# zapojeni.net
KiCad netlist of a schematic drawn in EAGLE
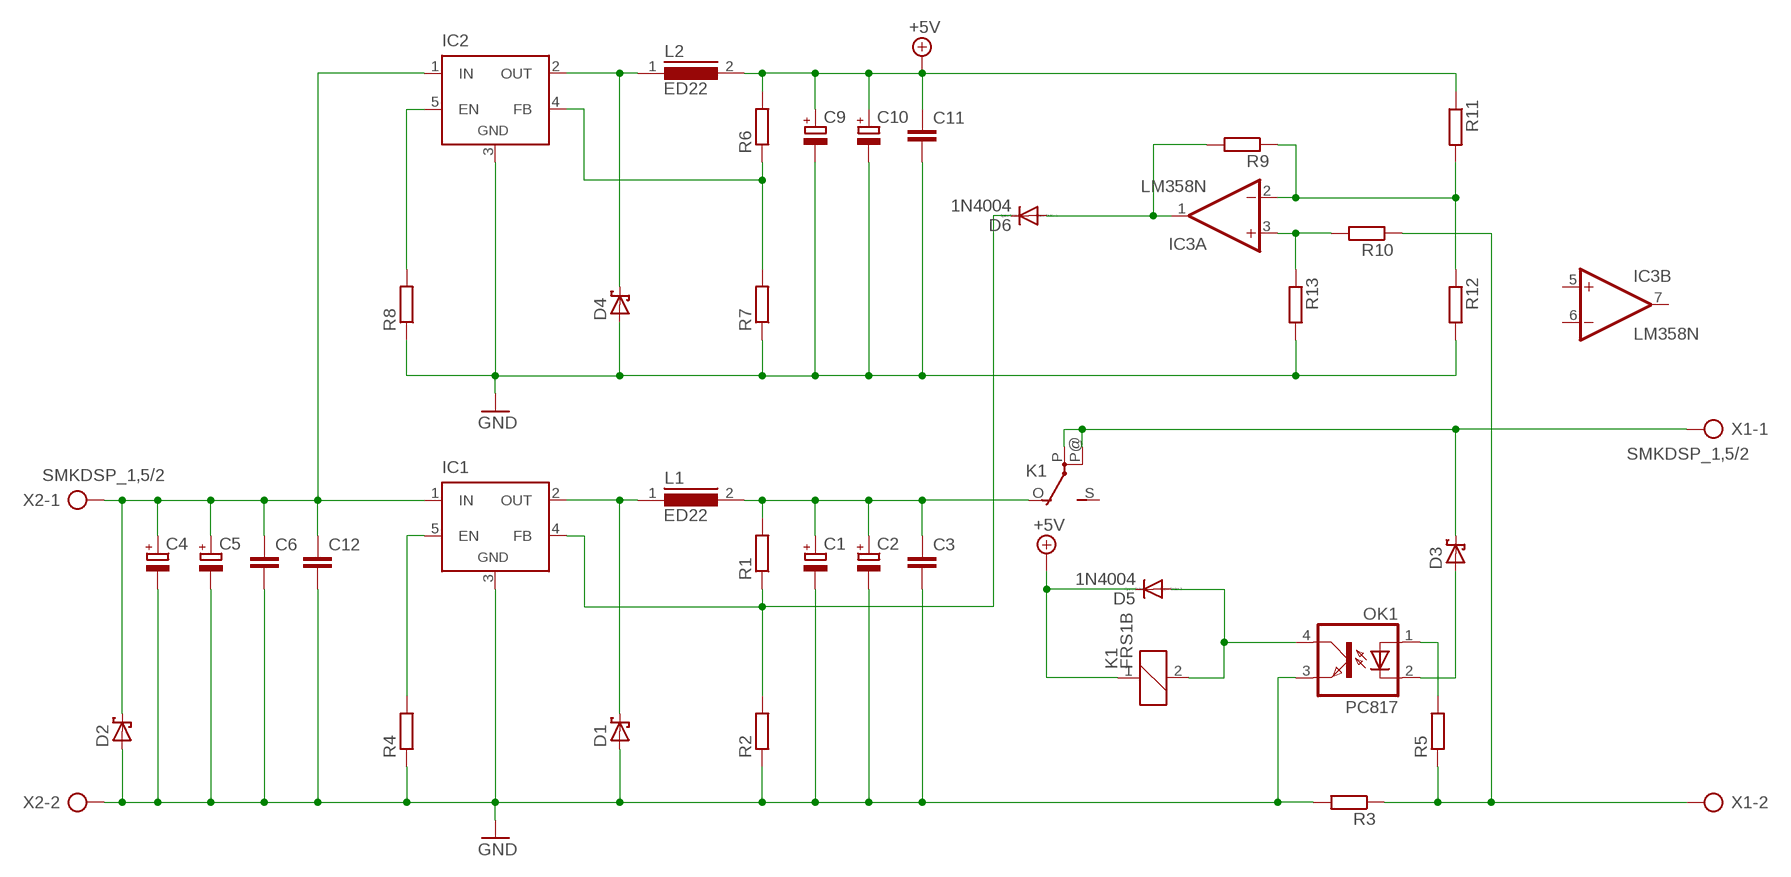
[diagram p0: schematic, sheet 1]

(export (version "E")
  (design (tool "Eeschema 10.0.6"))
  (components
    (comp (ref "C1")
      (value "CPOL-EUE5-8.5")
      (footprint "eagle-import:E5-8,5")
      (libsource (lib "eagle-import") (part "CPOL-EUE5-8.5"))
    )
    (comp (ref "C2")
      (value "CPOL-EUE5-8.5")
      (footprint "eagle-import:E5-8,5")
      (libsource (lib "eagle-import") (part "CPOL-EUE5-8.5"))
    )
    (comp (ref "C3")
      (value "C-EU050-035X075")
      (footprint "eagle-import:C050-035X075")
      (libsource (lib "eagle-import") (part "C-EU050-035X075"))
    )
    (comp (ref "C4")
      (value "CPOL-EUE5-8.5")
      (footprint "eagle-import:E5-8,5")
      (libsource (lib "eagle-import") (part "CPOL-EUE5-8.5"))
    )
    (comp (ref "C5")
      (value "CPOL-EUE5-8.5")
      (footprint "eagle-import:E5-8,5")
      (libsource (lib "eagle-import") (part "CPOL-EUE5-8.5"))
    )
    (comp (ref "C6")
      (value "C-EU050-035X075")
      (footprint "eagle-import:C050-035X075")
      (libsource (lib "eagle-import") (part "C-EU050-035X075"))
    )
    (comp (ref "C9")
      (value "CPOL-EUE5-8.5")
      (footprint "eagle-import:E5-8,5")
      (libsource (lib "eagle-import") (part "CPOL-EUE5-8.5"))
    )
    (comp (ref "C10")
      (value "CPOL-EUE5-8.5")
      (footprint "eagle-import:E5-8,5")
      (libsource (lib "eagle-import") (part "CPOL-EUE5-8.5"))
    )
    (comp (ref "C11")
      (value "C-EU050-035X075")
      (footprint "eagle-import:C050-035X075")
      (libsource (lib "eagle-import") (part "C-EU050-035X075"))
    )
    (comp (ref "C12")
      (value "C-EU050-035X075")
      (footprint "eagle-import:C050-035X075")
      (libsource (lib "eagle-import") (part "C-EU050-035X075"))
    )
    (comp (ref "D1")
      (value "SCHOTTKY-DIODEDO201T15")
      (footprint "eagle-import:DO201T15")
      (libsource (lib "eagle-import") (part "SCHOTTKY-DIODEDO201T15"))
    )
    (comp (ref "D2")
      (value "SCHOTTKY-DIODEDO201T15")
      (footprint "eagle-import:DO201T15")
      (libsource (lib "eagle-import") (part "SCHOTTKY-DIODEDO201T15"))
    )
    (comp (ref "D3")
      (value "SCHOTTKY-DIODEDO201T15")
      (footprint "eagle-import:DO201T15")
      (libsource (lib "eagle-import") (part "SCHOTTKY-DIODEDO201T15"))
    )
    (comp (ref "D4")
      (value "SCHOTTKY-DIODEDO201T15")
      (footprint "eagle-import:DO201T15")
      (libsource (lib "eagle-import") (part "SCHOTTKY-DIODEDO201T15"))
    )
    (comp (ref "D5")
      (value "1N4004")
      (footprint "eagle-import:DO41-10")
      (libsource (lib "eagle-import") (part "1N4004"))
    )
    (comp (ref "D6")
      (value "1N4004")
      (footprint "eagle-import:DO41-10")
      (libsource (lib "eagle-import") (part "1N4004"))
    )
    (comp (ref "IC1")
      (value "LM2596TH")
      (footprint "eagle-import:TO220-52")
      (libsource (lib "eagle-import") (part "LM2596TH"))
    )
    (comp (ref "IC2")
      (value "LM2596TH")
      (footprint "eagle-import:TO220-52")
      (libsource (lib "eagle-import") (part "LM2596TH"))
    )
    (comp (ref "IC3")
      (value "LM358N")
      (footprint "eagle-import:DIL08")
      (libsource (lib "eagle-import") (part "LM358N"))
    )
    (comp (ref "K1")
      (value "FRS1B")
      (footprint "eagle-import:FRS1B")
      (libsource (lib "eagle-import") (part "FRS1B"))
    )
    (comp (ref "L1")
      (value "ED22")
      (footprint "eagle-import:ED22")
      (libsource (lib "eagle-import") (part "ED22"))
    )
    (comp (ref "L2")
      (value "ED22")
      (footprint "eagle-import:ED22")
      (libsource (lib "eagle-import") (part "ED22"))
    )
    (comp (ref "OK1")
      (value "PC817")
      (footprint "eagle-import:DIL04")
      (fields (field (name "MPN") "PC817X4J000F"))
      (libsource (lib "eagle-import") (part "PC817"))
    )
    (comp (ref "R1")
      (value "R-EU_0207/10")
      (footprint "eagle-import:0207_10")
      (libsource (lib "eagle-import") (part "R-EU_0207/10"))
    )
    (comp (ref "R2")
      (value "R-EU_0207/10")
      (footprint "eagle-import:0207_10")
      (libsource (lib "eagle-import") (part "R-EU_0207/10"))
    )
    (comp (ref "R3")
      (value "R-EU_0207/10")
      (footprint "eagle-import:0207_10")
      (libsource (lib "eagle-import") (part "R-EU_0207/10"))
    )
    (comp (ref "R4")
      (value "R-EU_0207/10")
      (footprint "eagle-import:0207_10")
      (libsource (lib "eagle-import") (part "R-EU_0207/10"))
    )
    (comp (ref "R5")
      (value "R-EU_0207/10")
      (footprint "eagle-import:0207_10")
      (libsource (lib "eagle-import") (part "R-EU_0207/10"))
    )
    (comp (ref "R6")
      (value "R-EU_0207/10")
      (footprint "eagle-import:0207_10")
      (libsource (lib "eagle-import") (part "R-EU_0207/10"))
    )
    (comp (ref "R7")
      (value "R-EU_0207/10")
      (footprint "eagle-import:0207_10")
      (libsource (lib "eagle-import") (part "R-EU_0207/10"))
    )
    (comp (ref "R8")
      (value "R-EU_0207/10")
      (footprint "eagle-import:0207_10")
      (libsource (lib "eagle-import") (part "R-EU_0207/10"))
    )
    (comp (ref "R9")
      (value "R-EU_0207/10")
      (footprint "eagle-import:0207_10")
      (libsource (lib "eagle-import") (part "R-EU_0207/10"))
    )
    (comp (ref "R10")
      (value "R-EU_0207/10")
      (footprint "eagle-import:0207_10")
      (libsource (lib "eagle-import") (part "R-EU_0207/10"))
    )
    (comp (ref "R11")
      (value "R-EU_0207/10")
      (footprint "eagle-import:0207_10")
      (libsource (lib "eagle-import") (part "R-EU_0207/10"))
    )
    (comp (ref "R12")
      (value "R-EU_0207/10")
      (footprint "eagle-import:0207_10")
      (libsource (lib "eagle-import") (part "R-EU_0207/10"))
    )
    (comp (ref "R13")
      (value "R-EU_0207/10")
      (footprint "eagle-import:0207_10")
      (libsource (lib "eagle-import") (part "R-EU_0207/10"))
    )
    (comp (ref "X1")
      (value "SMKDSP_1,5/2")
      (footprint "eagle-import:SMKDSP_1,5_2")
      (fields (field (name "MF") "FARNELL") (field (name "MPN") "1733570"))
      (libsource (lib "eagle-import") (part "SMKDSP_1,5/2"))
    )
    (comp (ref "X2")
      (value "SMKDSP_1,5/2")
      (footprint "eagle-import:SMKDSP_1,5_2")
      (fields (field (name "MF") "FARNELL") (field (name "MPN") "1733570"))
      (libsource (lib "eagle-import") (part "SMKDSP_1,5/2"))
    )
  )
  (nets
    (net (code "1") (name "+5V") (class "Default")
      (node (ref "C10") (pin "+") (pinfunction "+_+") (pintype "passive"))
      (node (ref "C11") (pin "1") (pinfunction "1_1") (pintype "passive"))
      (node (ref "C9") (pin "+") (pinfunction "+_+") (pintype "passive"))
      (node (ref "D5") (pin "C") (pinfunction "C_C") (pintype "passive"))
      (node (ref "K1") (pin "1") (pinfunction "1_1") (pintype "passive"))
      (node (ref "L2") (pin "2") (pinfunction "2_2") (pintype "passive"))
      (node (ref "R11") (pin "1") (pinfunction "1_1") (pintype "passive"))
      (node (ref "R6") (pin "2") (pinfunction "2_2") (pintype "passive"))
    )
    (net (code "2") (name "GND") (class "Default")
      (node (ref "C1") (pin "-") (pinfunction "-_-") (pintype "passive"))
      (node (ref "C10") (pin "-") (pinfunction "-_-") (pintype "passive"))
      (node (ref "C11") (pin "2") (pinfunction "2_2") (pintype "passive"))
      (node (ref "C12") (pin "2") (pinfunction "2_2") (pintype "passive"))
      (node (ref "C2") (pin "-") (pinfunction "-_-") (pintype "passive"))
      (node (ref "C3") (pin "2") (pinfunction "2_2") (pintype "passive"))
      (node (ref "C4") (pin "-") (pinfunction "-_-") (pintype "passive"))
      (node (ref "C5") (pin "-") (pinfunction "-_-") (pintype "passive"))
      (node (ref "C6") (pin "2") (pinfunction "2_2") (pintype "passive"))
      (node (ref "C9") (pin "-") (pinfunction "-_-") (pintype "passive"))
      (node (ref "D1") (pin "A") (pinfunction "A_A") (pintype "passive"))
      (node (ref "D2") (pin "A") (pinfunction "A_A") (pintype "passive"))
      (node (ref "D4") (pin "A") (pinfunction "A_A") (pintype "passive"))
      (node (ref "IC1") (pin "3") (pinfunction "GND_3") (pintype "power_in"))
      (node (ref "IC2") (pin "3") (pinfunction "GND_3") (pintype "power_in"))
      (node (ref "OK1") (pin "3") (pinfunction "EMIT_3") (pintype "passive"))
      (node (ref "R12") (pin "2") (pinfunction "2_2") (pintype "passive"))
      (node (ref "R13") (pin "2") (pinfunction "2_2") (pintype "passive"))
      (node (ref "R2") (pin "1") (pinfunction "1_1") (pintype "passive"))
      (node (ref "R3") (pin "2") (pinfunction "2_2") (pintype "passive"))
      (node (ref "R4") (pin "1") (pinfunction "1_1") (pintype "passive"))
      (node (ref "R7") (pin "1") (pinfunction "1_1") (pintype "passive"))
      (node (ref "R8") (pin "1") (pinfunction "1_1") (pintype "passive"))
      (node (ref "X2") (pin "2") (pinfunction "KL_2") (pintype "passive"))
    )
    (net (code "3") (name "Net-(C1-Pad+)") (class "Default")
      (node (ref "C1") (pin "+") (pinfunction "+_+") (pintype "passive"))
      (node (ref "C2") (pin "+") (pinfunction "+_+") (pintype "passive"))
      (node (ref "C3") (pin "1") (pinfunction "1_1") (pintype "passive"))
      (node (ref "K1") (pin "O") (pinfunction "O_O") (pintype "passive"))
      (node (ref "L1") (pin "2") (pinfunction "2_2") (pintype "passive"))
      (node (ref "R1") (pin "2") (pinfunction "2_2") (pintype "passive"))
    )
    (net (code "4") (name "Net-(IC1-EN)") (class "Default")
      (node (ref "IC1") (pin "5") (pinfunction "EN_5") (pintype "input"))
      (node (ref "R4") (pin "2") (pinfunction "2_2") (pintype "passive"))
    )
    (net (code "5") (name "Net-(IC1-FB)") (class "Default")
      (node (ref "D6") (pin "C") (pinfunction "C_C") (pintype "passive"))
      (node (ref "IC1") (pin "4") (pinfunction "FB_4") (pintype "input"))
      (node (ref "R1") (pin "1") (pinfunction "1_1") (pintype "passive"))
      (node (ref "R2") (pin "2") (pinfunction "2_2") (pintype "passive"))
    )
    (net (code "6") (name "Net-(IC1-IN)") (class "Default")
      (node (ref "C12") (pin "1") (pinfunction "1_1") (pintype "passive"))
      (node (ref "C4") (pin "+") (pinfunction "+_+") (pintype "passive"))
      (node (ref "C5") (pin "+") (pinfunction "+_+") (pintype "passive"))
      (node (ref "C6") (pin "1") (pinfunction "1_1") (pintype "passive"))
      (node (ref "D2") (pin "C") (pinfunction "C_C") (pintype "passive"))
      (node (ref "IC1") (pin "1") (pinfunction "IN_1") (pintype "input"))
      (node (ref "IC2") (pin "1") (pinfunction "IN_1") (pintype "input"))
      (node (ref "X2") (pin "1") (pinfunction "KL_1") (pintype "passive"))
    )
    (net (code "7") (name "Net-(IC1-OUT)") (class "Default")
      (node (ref "D1") (pin "C") (pinfunction "C_C") (pintype "passive"))
      (node (ref "IC1") (pin "2") (pinfunction "OUT_2") (pintype "output"))
      (node (ref "L1") (pin "1") (pinfunction "1_1") (pintype "passive"))
    )
    (net (code "8") (name "Net-(IC2-EN)") (class "Default")
      (node (ref "IC2") (pin "5") (pinfunction "EN_5") (pintype "input"))
      (node (ref "R8") (pin "2") (pinfunction "2_2") (pintype "passive"))
    )
    (net (code "9") (name "Net-(IC2-FB)") (class "Default")
      (node (ref "IC2") (pin "4") (pinfunction "FB_4") (pintype "input"))
      (node (ref "R6") (pin "1") (pinfunction "1_1") (pintype "passive"))
      (node (ref "R7") (pin "2") (pinfunction "2_2") (pintype "passive"))
    )
    (net (code "10") (name "Net-(IC2-OUT)") (class "Default")
      (node (ref "D4") (pin "C") (pinfunction "C_C") (pintype "passive"))
      (node (ref "IC2") (pin "2") (pinfunction "OUT_2") (pintype "output"))
      (node (ref "L2") (pin "1") (pinfunction "1_1") (pintype "passive"))
    )
    (net (code "11") (name "Net-(IC3A-+IN)") (class "Default")
      (node (ref "IC3") (pin "3") (pinfunction "+IN_3") (pintype "input"))
      (node (ref "R10") (pin "2") (pinfunction "2_2") (pintype "passive"))
      (node (ref "R13") (pin "1") (pinfunction "1_1") (pintype "passive"))
    )
    (net (code "12") (name "Net-(IC3A--IN)") (class "Default")
      (node (ref "IC3") (pin "2") (pinfunction "-IN_2") (pintype "input"))
      (node (ref "R11") (pin "2") (pinfunction "2_2") (pintype "passive"))
      (node (ref "R12") (pin "1") (pinfunction "1_1") (pintype "passive"))
      (node (ref "R9") (pin "1") (pinfunction "1_1") (pintype "passive"))
    )
    (net (code "13") (name "Net-(IC3A-OUT)") (class "Default")
      (node (ref "D6") (pin "A") (pinfunction "A_A") (pintype "passive"))
      (node (ref "IC3") (pin "1") (pinfunction "OUT_1") (pintype "output"))
      (node (ref "R9") (pin "2") (pinfunction "2_2") (pintype "passive"))
    )
    (net (code "14") (name "Net-(OK1-A)") (class "Default")
      (node (ref "OK1") (pin "1") (pinfunction "A_1") (pintype "passive"))
      (node (ref "R5") (pin "2") (pinfunction "2_2") (pintype "passive"))
    )
    (net (code "15") (name "Net-(OK1-C)") (class "Default")
      (node (ref "D3") (pin "A") (pinfunction "A_A") (pintype "passive"))
      (node (ref "OK1") (pin "2") (pinfunction "C_2") (pintype "passive"))
    )
    (net (code "16") (name "Net-(OK1-COL)") (class "Default")
      (node (ref "D5") (pin "A") (pinfunction "A_A") (pintype "passive"))
      (node (ref "K1") (pin "2") (pinfunction "2_2") (pintype "passive"))
      (node (ref "OK1") (pin "4") (pinfunction "COL_4") (pintype "passive"))
    )
    (net (code "17") (name "Net-(X1A-KL)") (class "Default")
      (node (ref "D3") (pin "C") (pinfunction "C_C") (pintype "passive"))
      (node (ref "K1") (pin "P") (pinfunction "P_P") (pintype "passive"))
      (node (ref "K1") (pin "P@") (pinfunction "P_P@") (pintype "passive"))
      (node (ref "X1") (pin "1") (pinfunction "KL_1") (pintype "passive"))
    )
    (net (code "18") (name "Net-(X1B-KL)") (class "Default")
      (node (ref "R10") (pin "1") (pinfunction "1_1") (pintype "passive"))
      (node (ref "R3") (pin "1") (pinfunction "1_1") (pintype "passive"))
      (node (ref "R5") (pin "1") (pinfunction "1_1") (pintype "passive"))
      (node (ref "X1") (pin "2") (pinfunction "KL_2") (pintype "passive"))
    )
    (net (code "19") (name "unconnected-(IC3B-+IN-Pad5)") (class "Default")
      (node (ref "IC3") (pin "5") (pinfunction "+IN_5") (pintype "input"))
    )
    (net (code "20") (name "unconnected-(IC3B--IN-Pad6)") (class "Default")
      (node (ref "IC3") (pin "6") (pinfunction "-IN_6") (pintype "input"))
    )
    (net (code "21") (name "unconnected-(IC3B-OUT-Pad7)") (class "Default")
      (node (ref "IC3") (pin "7") (pinfunction "OUT_7") (pintype "output"))
    )
    (net (code "22") (name "unconnected-(K1-PadS)") (class "Default")
      (node (ref "K1") (pin "S") (pinfunction "S_S") (pintype "passive"))
    )
  )
)
